# ultrasonic_send.net
KiCad netlist of a schematic drawn in EAGLE
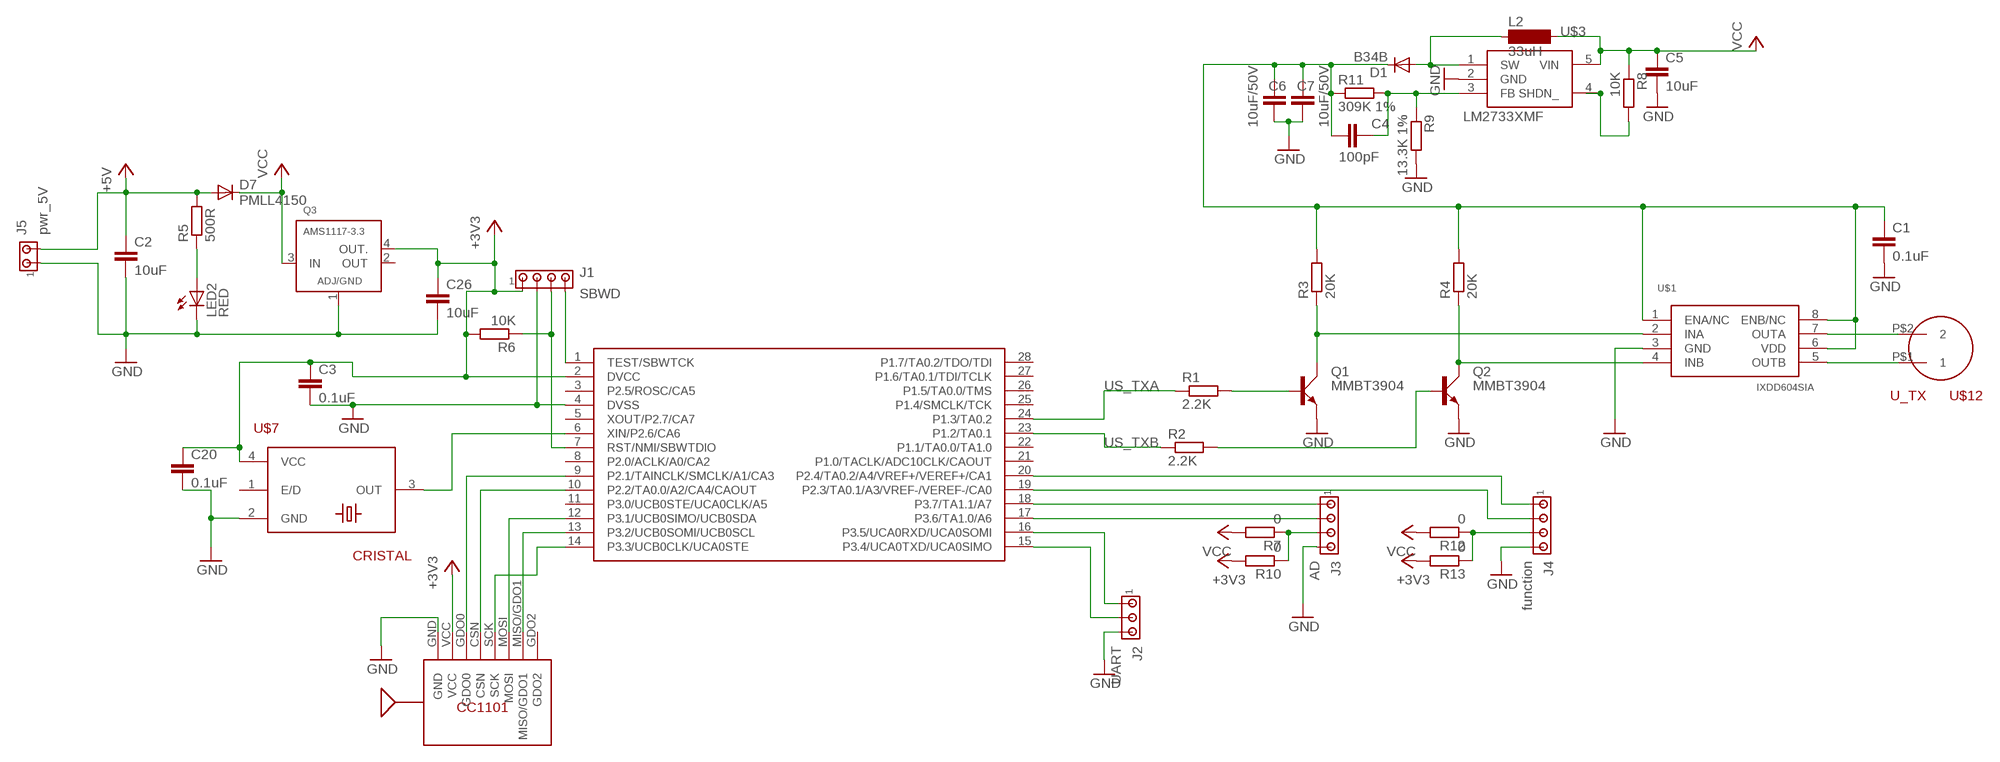
[diagram p0: schematic, sheet 1]

(export (version "E")
  (design (tool "Eeschema 10.0.6"))
  (components
    (comp (ref "C1")
      (value "0.1uF")
      (footprint "eagle-import:C0805")
      (libsource (lib "eagle-import") (part "C-EUC0805"))
    )
    (comp (ref "C2")
      (value "10uF")
      (footprint "eagle-import:C0805")
      (libsource (lib "eagle-import") (part "C-EUC0805"))
    )
    (comp (ref "C3")
      (value "0.1uF")
      (footprint "eagle-import:C0805")
      (libsource (lib "eagle-import") (part "C-EUC0805"))
    )
    (comp (ref "C4")
      (value "100pF")
      (footprint "eagle-import:C0805")
      (libsource (lib "eagle-import") (part "C-EUC0805"))
    )
    (comp (ref "C5")
      (value "10uF")
      (footprint "eagle-import:C0805")
      (libsource (lib "eagle-import") (part "C-EUC0805"))
    )
    (comp (ref "C6")
      (value "10uF/50V")
      (footprint "eagle-import:C1210")
      (libsource (lib "eagle-import") (part "C-EUC1210"))
    )
    (comp (ref "C7")
      (value "10uF/50V")
      (footprint "eagle-import:C1210")
      (libsource (lib "eagle-import") (part "C-EUC1210"))
    )
    (comp (ref "C20")
      (value "0.1uF")
      (footprint "eagle-import:C0805")
      (libsource (lib "eagle-import") (part "C-EUC0805"))
    )
    (comp (ref "C26")
      (value "10uF")
      (footprint "eagle-import:C0805")
      (libsource (lib "eagle-import") (part "C-EUC0805"))
    )
    (comp (ref "D1")
      (value "B34B")
      (footprint "eagle-import:GF1")
      (libsource (lib "eagle-import") (part "DIODE-GF1"))
    )
    (comp (ref "D7")
      (value "PMLL4150")
      (footprint "eagle-import:SOD80C")
      (libsource (lib "eagle-import") (part "PMLL4150"))
    )
    (comp (ref "J1")
      (value "SBWD")
      (footprint "eagle-import:10X04MTA")
      (libsource (lib "eagle-import") (part "MTA04-100"))
    )
    (comp (ref "J2")
      (value "UART")
      (footprint "eagle-import:10X03MTA")
      (libsource (lib "eagle-import") (part "MTA03-100"))
    )
    (comp (ref "J3")
      (value "AD")
      (footprint "eagle-import:10X04MTA")
      (libsource (lib "eagle-import") (part "MTA04-100"))
    )
    (comp (ref "J4")
      (value "function")
      (footprint "eagle-import:10X04MTA")
      (libsource (lib "eagle-import") (part "MTA04-100"))
    )
    (comp (ref "J5")
      (value "pwr_5V")
      (footprint "eagle-import:10X02MTA")
      (libsource (lib "eagle-import") (part "MTA02-100"))
    )
    (comp (ref "L2")
      (value "33uH")
      (footprint "eagle-import:MS85")
      (libsource (lib "eagle-import") (part "MS85"))
    )
    (comp (ref "LED2")
      (value "RED")
      (footprint "eagle-import:SML0805")
      (libsource (lib "eagle-import") (part "LEDSML0805"))
    )
    (comp (ref "Q1")
      (value "MMBT3904")
      (footprint "eagle-import:SOT23")
      (libsource (lib "eagle-import") (part "MMBT3904"))
    )
    (comp (ref "Q2")
      (value "MMBT3904")
      (footprint "eagle-import:SOT23")
      (libsource (lib "eagle-import") (part "MMBT3904"))
    )
    (comp (ref "Q3")
      (value "AMS1117-3.3")
      (footprint "eagle-import:SOT223-4")
      (libsource (lib "eagle-import") (part "TLV1117"))
    )
    (comp (ref "R1")
      (value "2.2K")
      (footprint "eagle-import:R0805")
      (libsource (lib "eagle-import") (part "R-EU_R0805"))
    )
    (comp (ref "R2")
      (value "2.2K")
      (footprint "eagle-import:R0805")
      (libsource (lib "eagle-import") (part "R-EU_R0805"))
    )
    (comp (ref "R3")
      (value "20K")
      (footprint "eagle-import:R0603")
      (libsource (lib "eagle-import") (part "R-EU_R0603"))
    )
    (comp (ref "R4")
      (value "20K")
      (footprint "eagle-import:R0603")
      (libsource (lib "eagle-import") (part "R-EU_R0603"))
    )
    (comp (ref "R5")
      (value "500R")
      (footprint "eagle-import:R0603")
      (libsource (lib "eagle-import") (part "R-EU_R0603"))
    )
    (comp (ref "R6")
      (value "10K")
      (footprint "eagle-import:R0603")
      (libsource (lib "eagle-import") (part "R-EU_R0603"))
    )
    (comp (ref "R7")
      (value "0")
      (footprint "eagle-import:R0603")
      (libsource (lib "eagle-import") (part "R-EU_R0603"))
    )
    (comp (ref "R8")
      (value "10K")
      (footprint "eagle-import:R0603")
      (libsource (lib "eagle-import") (part "R-EU_R0603"))
    )
    (comp (ref "R9")
      (value "13.3K 1%")
      (footprint "eagle-import:R0603")
      (libsource (lib "eagle-import") (part "R-EU_R0603"))
    )
    (comp (ref "R10")
      (value "0")
      (footprint "eagle-import:R0603")
      (libsource (lib "eagle-import") (part "R-EU_R0603"))
    )
    (comp (ref "R11")
      (value "309K 1%")
      (footprint "eagle-import:R0603")
      (libsource (lib "eagle-import") (part "R-EU_R0603"))
    )
    (comp (ref "R12")
      (value "0")
      (footprint "eagle-import:R0603")
      (libsource (lib "eagle-import") (part "R-EU_R0603"))
    )
    (comp (ref "R13")
      (value "0")
      (footprint "eagle-import:R0603")
      (libsource (lib "eagle-import") (part "R-EU_R0603"))
    )
    (comp (ref "U$1")
      (value "IXDD604SIA")
      (footprint "eagle-import:SO8")
      (libsource (lib "eagle-import") (part "IXDD604SIA"))
    )
    (comp (ref "U$2")
      (value "MSP430F2112")
      (footprint "eagle-import:PW_R-PDSO-G28")
      (libsource (lib "eagle-import") (part "MSP430F2112"))
    )
    (comp (ref "U$3")
      (value "LM2733XMF")
      (footprint "eagle-import:SOT23-DBV")
      (libsource (lib "eagle-import") (part "LM2733XMF"))
    )
    (comp (ref "U$4")
      (value "CC1101")
      (footprint "eagle-import:CC1101")
      (libsource (lib "eagle-import") (part "CC1101"))
    )
    (comp (ref "U$7")
      (value "CRISTAL")
      (footprint "eagle-import:CTS406")
      (libsource (lib "eagle-import") (part "CRISTAL"))
    )
    (comp (ref "U$12")
      (value "U_TX")
      (footprint "eagle-import:ULTRASONIC")
      (libsource (lib "eagle-import") (part "ULTRASONIC"))
    )
  )
  (nets
    (net (code "1") (name "+3V3") (class "Default")
      (node (ref "C20") (pin "1") (pinfunction "1_1") (pintype "passive"))
      (node (ref "C26") (pin "1") (pinfunction "1_1") (pintype "passive"))
      (node (ref "C3") (pin "1") (pinfunction "1_1") (pintype "passive"))
      (node (ref "J1") (pin "1") (pinfunction "1_1") (pintype "passive"))
      (node (ref "Q3") (pin "4") (pinfunction "OUT._4") (pintype "power_in"))
      (node (ref "R10") (pin "2") (pinfunction "2_2") (pintype "passive"))
      (node (ref "R13") (pin "2") (pinfunction "2_2") (pintype "passive"))
      (node (ref "R6") (pin "2") (pinfunction "2_2") (pintype "passive"))
      (node (ref "U$2") (pin "2") (pinfunction "DVCC_2") (pintype "bidirectional"))
      (node (ref "U$4") (pin "VCC") (pinfunction "VCC_VCC") (pintype "bidirectional"))
      (node (ref "U$7") (pin "4") (pinfunction "VCC_4") (pintype "power_in"))
    )
    (net (code "2") (name "+5V") (class "Default")
      (node (ref "C2") (pin "1") (pinfunction "1_1") (pintype "passive"))
      (node (ref "D7") (pin "A") (pinfunction "A_A") (pintype "passive"))
      (node (ref "J5") (pin "2") (pinfunction "2_2") (pintype "passive"))
      (node (ref "R5") (pin "2") (pinfunction "2_2") (pintype "passive"))
    )
    (net (code "3") (name "/OUT") (class "Default")
      (node (ref "Q3") (pin "2") (pinfunction "OUT_2") (pintype "power_in"))
    )
    (net (code "4") (name "/US_TXA") (class "Default")
      (node (ref "R1") (pin "1") (pinfunction "1_1") (pintype "passive"))
      (node (ref "U$2") (pin "24") (pinfunction "P1.3/TA0.2_24") (pintype "bidirectional"))
    )
    (net (code "5") (name "/US_TXB") (class "Default")
      (node (ref "R2") (pin "1") (pinfunction "1_1") (pintype "passive"))
      (node (ref "U$2") (pin "23") (pinfunction "P1.2/TA0.1_23") (pintype "bidirectional"))
    )
    (net (code "6") (name "GND") (class "Default")
      (node (ref "C1") (pin "2") (pinfunction "2_2") (pintype "passive"))
      (node (ref "C2") (pin "2") (pinfunction "2_2") (pintype "passive"))
      (node (ref "C20") (pin "2") (pinfunction "2_2") (pintype "passive"))
      (node (ref "C26") (pin "2") (pinfunction "2_2") (pintype "passive"))
      (node (ref "C3") (pin "2") (pinfunction "2_2") (pintype "passive"))
      (node (ref "C5") (pin "2") (pinfunction "2_2") (pintype "passive"))
      (node (ref "C6") (pin "2") (pinfunction "2_2") (pintype "passive"))
      (node (ref "C7") (pin "2") (pinfunction "2_2") (pintype "passive"))
      (node (ref "J1") (pin "2") (pinfunction "2_2") (pintype "passive"))
      (node (ref "J2") (pin "3") (pinfunction "3_3") (pintype "passive"))
      (node (ref "J3") (pin "4") (pinfunction "4_4") (pintype "passive"))
      (node (ref "J4") (pin "4") (pinfunction "4_4") (pintype "passive"))
      (node (ref "J5") (pin "1") (pinfunction "1_1") (pintype "passive"))
      (node (ref "LED2") (pin "C") (pinfunction "C_C") (pintype "passive"))
      (node (ref "Q1") (pin "2") (pinfunction "E_2") (pintype "passive"))
      (node (ref "Q2") (pin "2") (pinfunction "E_2") (pintype "passive"))
      (node (ref "Q3") (pin "1") (pinfunction "ADJ/GND_1") (pintype "bidirectional"))
      (node (ref "R9") (pin "2") (pinfunction "2_2") (pintype "passive"))
      (node (ref "U$1") (pin "3") (pinfunction "GND_3") (pintype "power_in"))
      (node (ref "U$2") (pin "4") (pinfunction "DVSS_4") (pintype "bidirectional"))
      (node (ref "U$3") (pin "2") (pinfunction "GND_2") (pintype "bidirectional"))
      (node (ref "U$4") (pin "GND") (pinfunction "GND_GND") (pintype "bidirectional"))
      (node (ref "U$7") (pin "2") (pinfunction "GND_2") (pintype "power_in"))
    )
    (net (code "7") (name "Net-(J3-Pad3)") (class "Default")
      (node (ref "J3") (pin "3") (pinfunction "3_3") (pintype "passive"))
      (node (ref "R10") (pin "1") (pinfunction "1_1") (pintype "passive"))
      (node (ref "R7") (pin "1") (pinfunction "1_1") (pintype "passive"))
    )
    (net (code "8") (name "Net-(J4-Pad3)") (class "Default")
      (node (ref "J4") (pin "3") (pinfunction "3_3") (pintype "passive"))
      (node (ref "R12") (pin "1") (pinfunction "1_1") (pintype "passive"))
      (node (ref "R13") (pin "1") (pinfunction "1_1") (pintype "passive"))
    )
    (net (code "9") (name "Net-(LED2-PadA)") (class "Default")
      (node (ref "LED2") (pin "A") (pinfunction "A_A") (pintype "passive"))
      (node (ref "R5") (pin "1") (pinfunction "1_1") (pintype "passive"))
    )
    (net (code "10") (name "Net-(Q1-B)") (class "Default")
      (node (ref "Q1") (pin "1") (pinfunction "B_1") (pintype "passive"))
      (node (ref "R1") (pin "2") (pinfunction "2_2") (pintype "passive"))
    )
    (net (code "11") (name "Net-(Q1-C)") (class "Default")
      (node (ref "Q1") (pin "3") (pinfunction "C_3") (pintype "passive"))
      (node (ref "R3") (pin "1") (pinfunction "1_1") (pintype "passive"))
      (node (ref "U$1") (pin "2") (pinfunction "INA_2") (pintype "input"))
    )
    (net (code "12") (name "Net-(Q2-B)") (class "Default")
      (node (ref "Q2") (pin "1") (pinfunction "B_1") (pintype "passive"))
      (node (ref "R2") (pin "2") (pinfunction "2_2") (pintype "passive"))
    )
    (net (code "13") (name "Net-(Q2-C)") (class "Default")
      (node (ref "Q2") (pin "3") (pinfunction "C_3") (pintype "passive"))
      (node (ref "R4") (pin "1") (pinfunction "1_1") (pintype "passive"))
      (node (ref "U$1") (pin "4") (pinfunction "INB_4") (pintype "input"))
    )
    (net (code "14") (name "Net-(U$1-ENA{slash}NC)") (class "Default")
      (node (ref "C1") (pin "1") (pinfunction "1_1") (pintype "passive"))
      (node (ref "C4") (pin "1") (pinfunction "1_1") (pintype "passive"))
      (node (ref "C6") (pin "1") (pinfunction "1_1") (pintype "passive"))
      (node (ref "C7") (pin "1") (pinfunction "1_1") (pintype "passive"))
      (node (ref "D1") (pin "C") (pinfunction "C_C") (pintype "passive"))
      (node (ref "R11") (pin "1") (pinfunction "1_1") (pintype "passive"))
      (node (ref "R3") (pin "2") (pinfunction "2_2") (pintype "passive"))
      (node (ref "R4") (pin "2") (pinfunction "2_2") (pintype "passive"))
      (node (ref "U$1") (pin "1") (pinfunction "ENA/NC_1") (pintype "bidirectional"))
      (node (ref "U$1") (pin "6") (pinfunction "VDD_6") (pintype "power_in"))
      (node (ref "U$1") (pin "8") (pinfunction "ENB/NC_8") (pintype "bidirectional"))
    )
    (net (code "15") (name "Net-(U$1-OUTA)") (class "Default")
      (node (ref "U$1") (pin "7") (pinfunction "OUTA_7") (pintype "output"))
      (node (ref "U$12") (pin "P$2") (pinfunction "2_P$2") (pintype "bidirectional"))
    )
    (net (code "16") (name "Net-(U$1-OUTB)") (class "Default")
      (node (ref "U$1") (pin "5") (pinfunction "OUTB_5") (pintype "output"))
      (node (ref "U$12") (pin "P$1") (pinfunction "1_P$1") (pintype "bidirectional"))
    )
    (net (code "17") (name "Net-(U$2-P2.1{slash}TAINCLK{slash}SMCLK{slash}A1{slash}CA3)") (class "Default")
      (node (ref "U$2") (pin "9") (pinfunction "P2.1/TAINCLK/SMCLK/A1/CA3_9") (pintype "bidirectional"))
      (node (ref "U$4") (pin "GDO0") (pinfunction "GDO0_GDO0") (pintype "bidirectional"))
    )
    (net (code "18") (name "Net-(U$2-P2.2{slash}TA0.0{slash}A2{slash}CA4{slash}CAOUT)") (class "Default")
      (node (ref "U$2") (pin "10") (pinfunction "P2.2/TA0.0/A2/CA4/CAOUT_10") (pintype "bidirectional"))
      (node (ref "U$4") (pin "CSN") (pinfunction "CSN_CSN") (pintype "bidirectional"))
    )
    (net (code "19") (name "Net-(U$2-P2.3{slash}TA0.1{slash}A3{slash}VREF-{slash}VEREF-{slash}CA0)") (class "Default")
      (node (ref "J4") (pin "2") (pinfunction "2_2") (pintype "passive"))
      (node (ref "U$2") (pin "19") (pinfunction "P2.3/TA0.1/A3/VREF-/VEREF-/CA0_19") (pintype "bidirectional"))
    )
    (net (code "20") (name "Net-(U$2-P2.4{slash}TA0.2{slash}A4{slash}VREF+{slash}VEREF+{slash}CA1)") (class "Default")
      (node (ref "J4") (pin "1") (pinfunction "1_1") (pintype "passive"))
      (node (ref "U$2") (pin "20") (pinfunction "P2.4/TA0.2/A4/VREF+/VEREF+/CA1_20") (pintype "bidirectional"))
    )
    (net (code "21") (name "Net-(U$2-P3.1{slash}UCB0SIMO{slash}UCB0SDA)") (class "Default")
      (node (ref "U$2") (pin "12") (pinfunction "P3.1/UCB0SIMO/UCB0SDA_12") (pintype "bidirectional"))
      (node (ref "U$4") (pin "MOSI") (pinfunction "MOSI_MOSI") (pintype "bidirectional"))
    )
    (net (code "22") (name "Net-(U$2-P3.2{slash}UCB0SOMI{slash}UCB0SCL)") (class "Default")
      (node (ref "U$2") (pin "13") (pinfunction "P3.2/UCB0SOMI/UCB0SCL_13") (pintype "bidirectional"))
      (node (ref "U$4") (pin "MISO/GDO1") (pinfunction "MISO/GDO1_MISO/GDO1") (pintype "bidirectional"))
    )
    (net (code "23") (name "Net-(U$2-P3.3{slash}UCB0CLK{slash}UCA0STE)") (class "Default")
      (node (ref "U$2") (pin "14") (pinfunction "P3.3/UCB0CLK/UCA0STE_14") (pintype "bidirectional"))
      (node (ref "U$4") (pin "SCK") (pinfunction "SCK_SCK") (pintype "bidirectional"))
    )
    (net (code "24") (name "Net-(U$2-P3.4{slash}UCA0TXD{slash}UCA0SIMO)") (class "Default")
      (node (ref "J2") (pin "2") (pinfunction "2_2") (pintype "passive"))
      (node (ref "U$2") (pin "15") (pinfunction "P3.4/UCA0TXD/UCA0SIMO_15") (pintype "bidirectional"))
    )
    (net (code "25") (name "Net-(U$2-P3.5{slash}UCA0RXD{slash}UCA0SOMI)") (class "Default")
      (node (ref "J2") (pin "1") (pinfunction "1_1") (pintype "passive"))
      (node (ref "U$2") (pin "16") (pinfunction "P3.5/UCA0RXD/UCA0SOMI_16") (pintype "bidirectional"))
    )
    (net (code "26") (name "Net-(U$2-P3.6{slash}TA1.0{slash}A6)") (class "Default")
      (node (ref "J3") (pin "2") (pinfunction "2_2") (pintype "passive"))
      (node (ref "U$2") (pin "17") (pinfunction "P3.6/TA1.0/A6_17") (pintype "bidirectional"))
    )
    (net (code "27") (name "Net-(U$2-P3.7{slash}TA1.1{slash}A7)") (class "Default")
      (node (ref "J3") (pin "1") (pinfunction "1_1") (pintype "passive"))
      (node (ref "U$2") (pin "18") (pinfunction "P3.7/TA1.1/A7_18") (pintype "bidirectional"))
    )
    (net (code "28") (name "Net-(U$2-RST{slash}NMI{slash}SBWTDIO)") (class "Default")
      (node (ref "J1") (pin "3") (pinfunction "3_3") (pintype "passive"))
      (node (ref "R6") (pin "1") (pinfunction "1_1") (pintype "passive"))
      (node (ref "U$2") (pin "7") (pinfunction "RST/NMI/SBWTDIO_7") (pintype "bidirectional"))
    )
    (net (code "29") (name "Net-(U$2-TEST{slash}SBWTCK)") (class "Default")
      (node (ref "J1") (pin "4") (pinfunction "4_4") (pintype "passive"))
      (node (ref "U$2") (pin "1") (pinfunction "TEST/SBWTCK_1") (pintype "bidirectional"))
    )
    (net (code "30") (name "Net-(U$2-XIN{slash}P2.6{slash}CA6)") (class "Default")
      (node (ref "U$2") (pin "6") (pinfunction "XIN/P2.6/CA6_6") (pintype "bidirectional"))
      (node (ref "U$7") (pin "3") (pinfunction "OUT_3") (pintype "output"))
    )
    (net (code "31") (name "Net-(U$3-FB)") (class "Default")
      (node (ref "C4") (pin "2") (pinfunction "2_2") (pintype "passive"))
      (node (ref "R11") (pin "2") (pinfunction "2_2") (pintype "passive"))
      (node (ref "R9") (pin "1") (pinfunction "1_1") (pintype "passive"))
      (node (ref "U$3") (pin "3") (pinfunction "FB_3") (pintype "input"))
    )
    (net (code "32") (name "Net-(U$3-SHDN_)") (class "Default")
      (node (ref "R8") (pin "2") (pinfunction "2_2") (pintype "passive"))
      (node (ref "U$3") (pin "4") (pinfunction "SHDN__4") (pintype "input"))
    )
    (net (code "33") (name "Net-(U$3-SW)") (class "Default")
      (node (ref "D1") (pin "A") (pinfunction "A_A") (pintype "passive"))
      (node (ref "L2") (pin "1") (pinfunction "1_1") (pintype "passive"))
      (node (ref "U$3") (pin "1") (pinfunction "SW_1") (pintype "output"))
    )
    (net (code "34") (name "VCC") (class "Default")
      (node (ref "C5") (pin "1") (pinfunction "1_1") (pintype "passive"))
      (node (ref "D7") (pin "C") (pinfunction "C_C") (pintype "passive"))
      (node (ref "L2") (pin "2") (pinfunction "2_2") (pintype "passive"))
      (node (ref "Q3") (pin "3") (pinfunction "IN_3") (pintype "power_in"))
      (node (ref "R12") (pin "2") (pinfunction "2_2") (pintype "passive"))
      (node (ref "R7") (pin "2") (pinfunction "2_2") (pintype "passive"))
      (node (ref "R8") (pin "1") (pinfunction "1_1") (pintype "passive"))
      (node (ref "U$3") (pin "5") (pinfunction "VIN_5") (pintype "bidirectional"))
    )
    (net (code "35") (name "unconnected-(U$2-P1.0{slash}TACLK{slash}ADC10CLK{slash}CAOUT-Pad21)") (class "Default")
      (node (ref "U$2") (pin "21") (pinfunction "P1.0/TACLK/ADC10CLK/CAOUT_21") (pintype "bidirectional"))
    )
    (net (code "36") (name "unconnected-(U$2-P1.1{slash}TA0.0{slash}TA1.0-Pad22)") (class "Default")
      (node (ref "U$2") (pin "22") (pinfunction "P1.1/TA0.0/TA1.0_22") (pintype "bidirectional"))
    )
    (net (code "37") (name "unconnected-(U$2-P1.4{slash}SMCLK{slash}TCK-Pad25)") (class "Default")
      (node (ref "U$2") (pin "25") (pinfunction "P1.4/SMCLK/TCK_25") (pintype "bidirectional"))
    )
    (net (code "38") (name "unconnected-(U$2-P1.5{slash}TA0.0{slash}TMS-Pad26)") (class "Default")
      (node (ref "U$2") (pin "26") (pinfunction "P1.5/TA0.0/TMS_26") (pintype "bidirectional"))
    )
    (net (code "39") (name "unconnected-(U$2-P1.6{slash}TA0.1{slash}TDI{slash}TCLK-Pad27)") (class "Default")
      (node (ref "U$2") (pin "27") (pinfunction "P1.6/TA0.1/TDI/TCLK_27") (pintype "bidirectional"))
    )
    (net (code "40") (name "unconnected-(U$2-P1.7{slash}TA0.2{slash}TDO{slash}TDI-Pad28)") (class "Default")
      (node (ref "U$2") (pin "28") (pinfunction "P1.7/TA0.2/TDO/TDI_28") (pintype "bidirectional"))
    )
    (net (code "41") (name "unconnected-(U$2-P2.0{slash}ACLK{slash}A0{slash}CA2-Pad8)") (class "Default")
      (node (ref "U$2") (pin "8") (pinfunction "P2.0/ACLK/A0/CA2_8") (pintype "bidirectional"))
    )
    (net (code "42") (name "unconnected-(U$2-P2.5{slash}ROSC{slash}CA5-Pad3)") (class "Default")
      (node (ref "U$2") (pin "3") (pinfunction "P2.5/ROSC/CA5_3") (pintype "bidirectional"))
    )
    (net (code "43") (name "unconnected-(U$2-P3.0{slash}UCB0STE{slash}UCA0CLK{slash}A5-Pad11)") (class "Default")
      (node (ref "U$2") (pin "11") (pinfunction "P3.0/UCB0STE/UCA0CLK/A5_11") (pintype "bidirectional"))
    )
    (net (code "44") (name "unconnected-(U$2-XOUT{slash}P2.7{slash}CA7-Pad5)") (class "Default")
      (node (ref "U$2") (pin "5") (pinfunction "XOUT/P2.7/CA7_5") (pintype "bidirectional"))
    )
    (net (code "45") (name "unconnected-(U$4-PadGDO2)") (class "Default")
      (node (ref "U$4") (pin "GDO2") (pinfunction "GDO2_GDO2") (pintype "bidirectional"))
    )
    (net (code "46") (name "unconnected-(U$7-E{slash}D-Pad1)") (class "Default")
      (node (ref "U$7") (pin "1") (pinfunction "E/D_1") (pintype "no_connect"))
    )
  )
)
